# photo-trigger.net
KiCad netlist of a schematic drawn in EAGLE
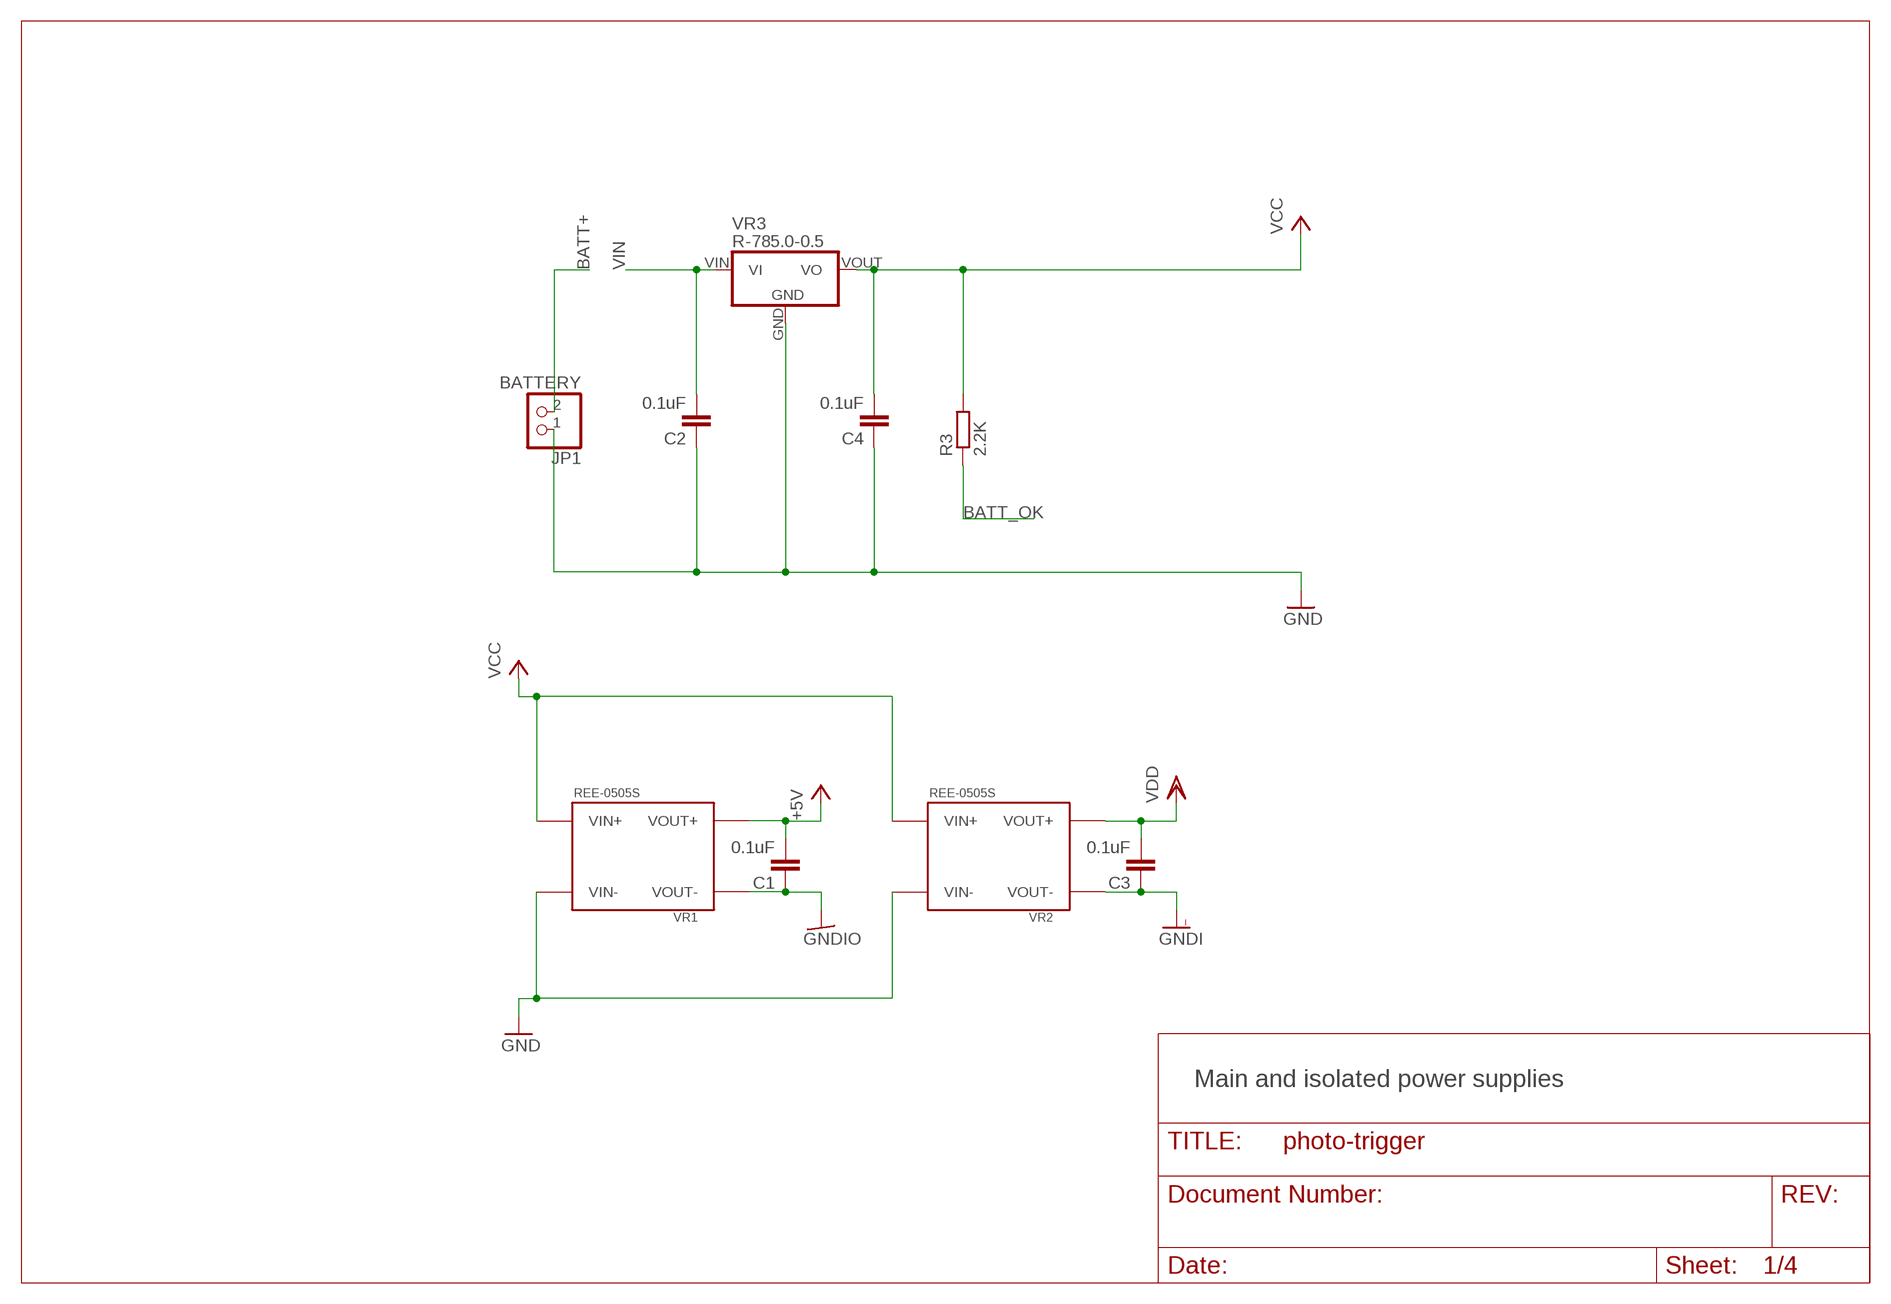
[diagram p0: schematic, sheet 1]
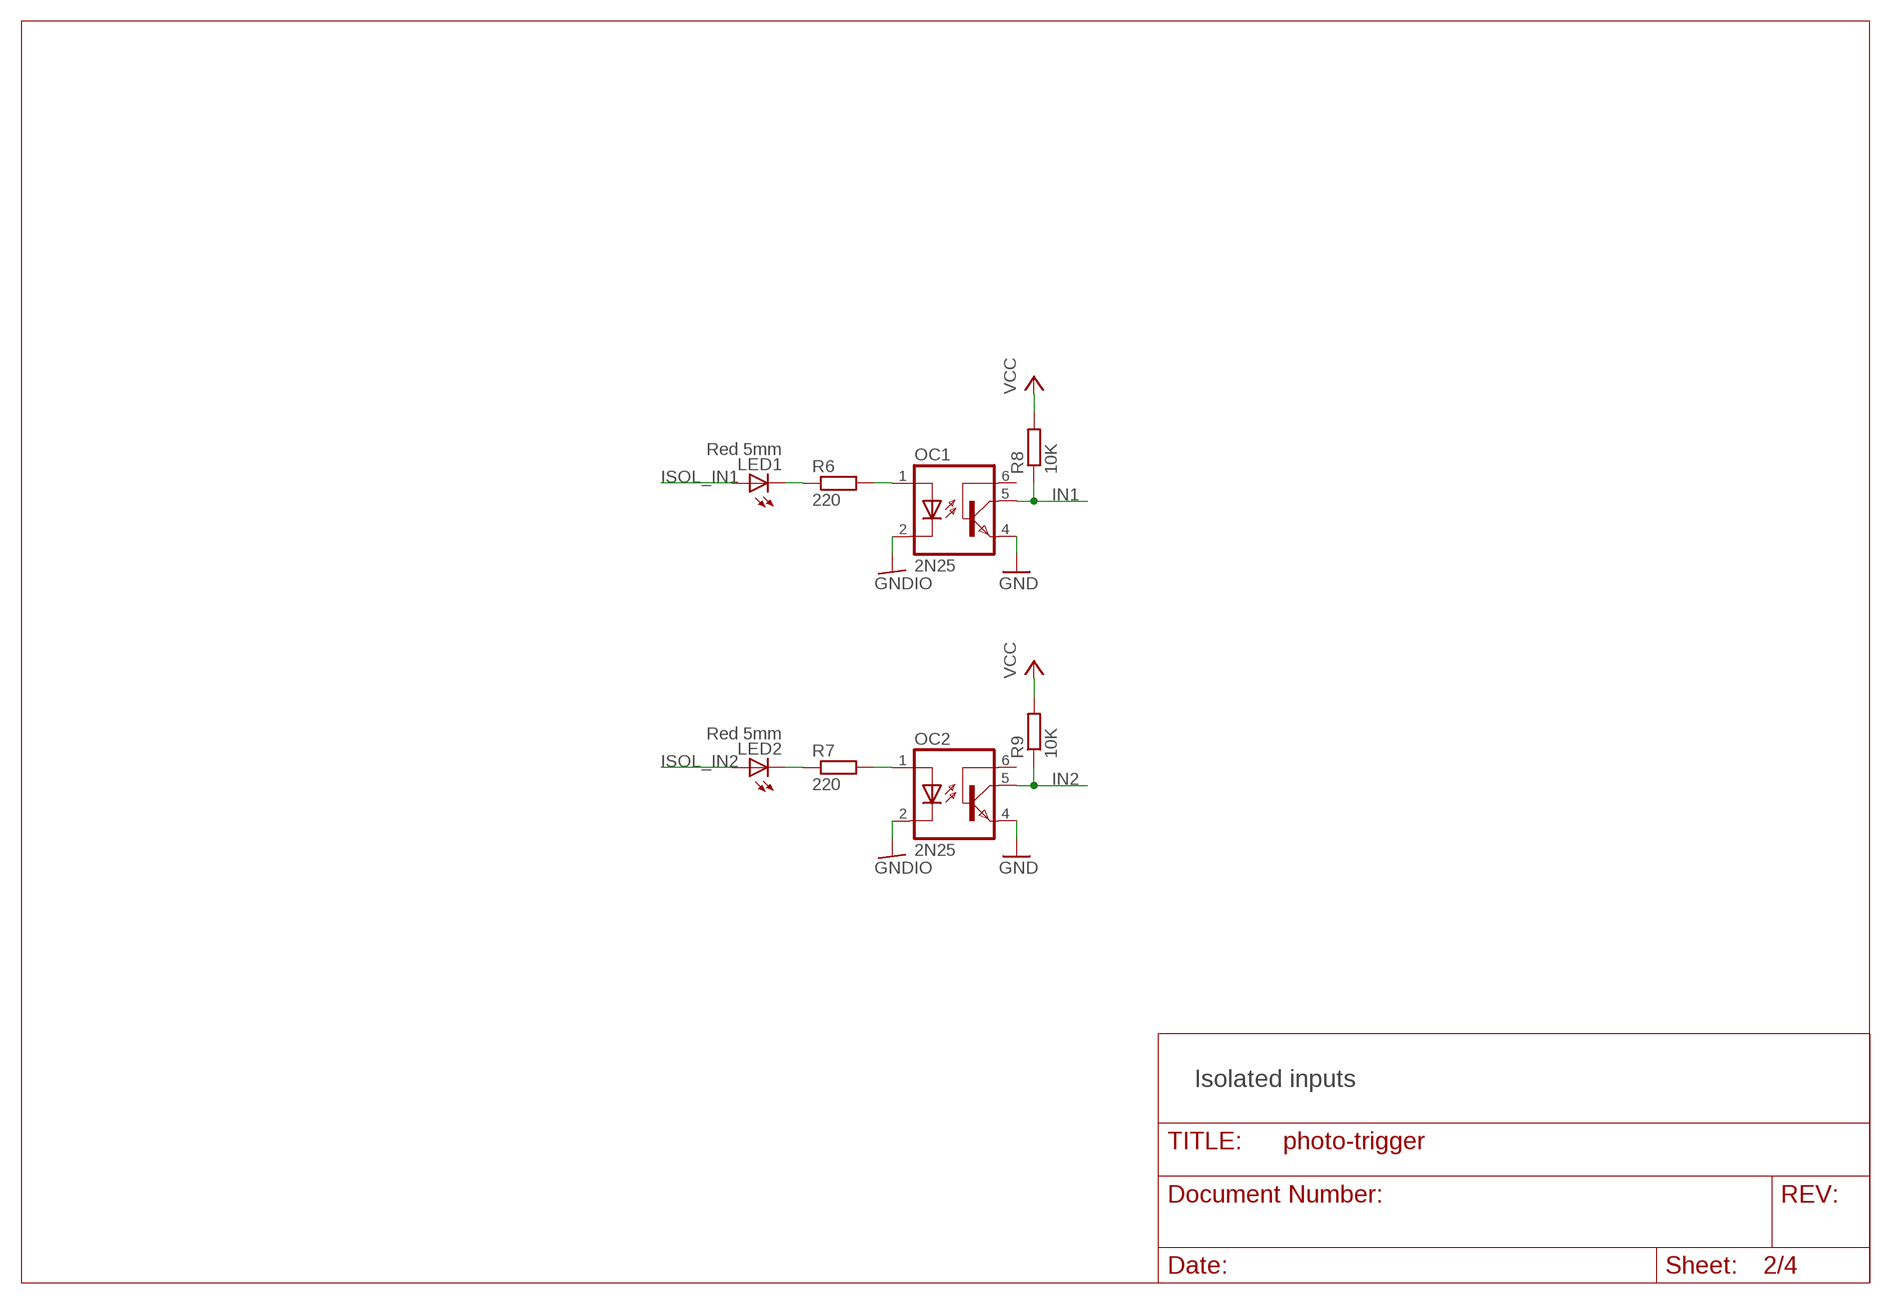
[diagram p1: schematic, sheet 2]
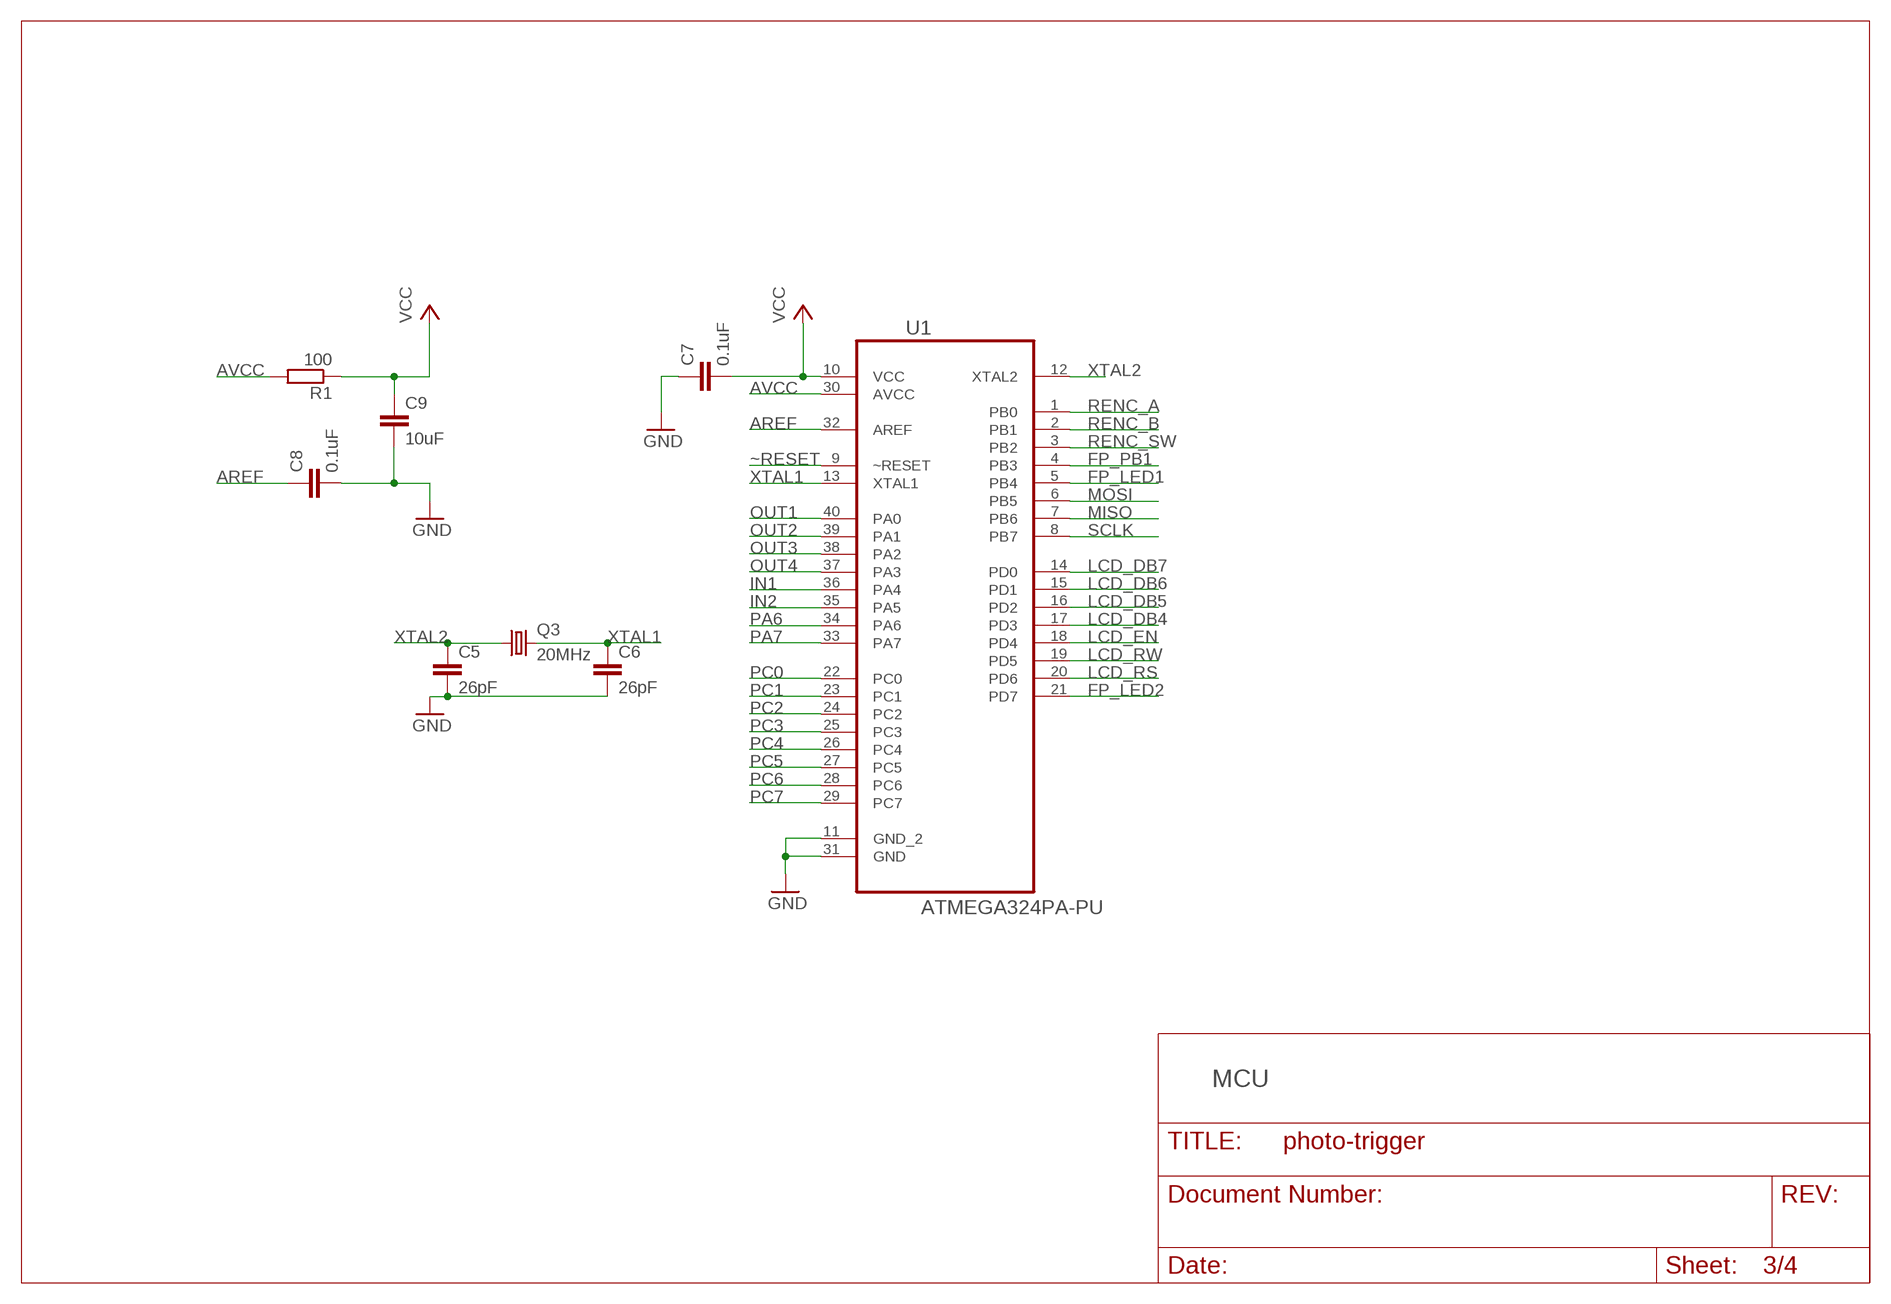
[diagram p2: schematic, sheet 3]
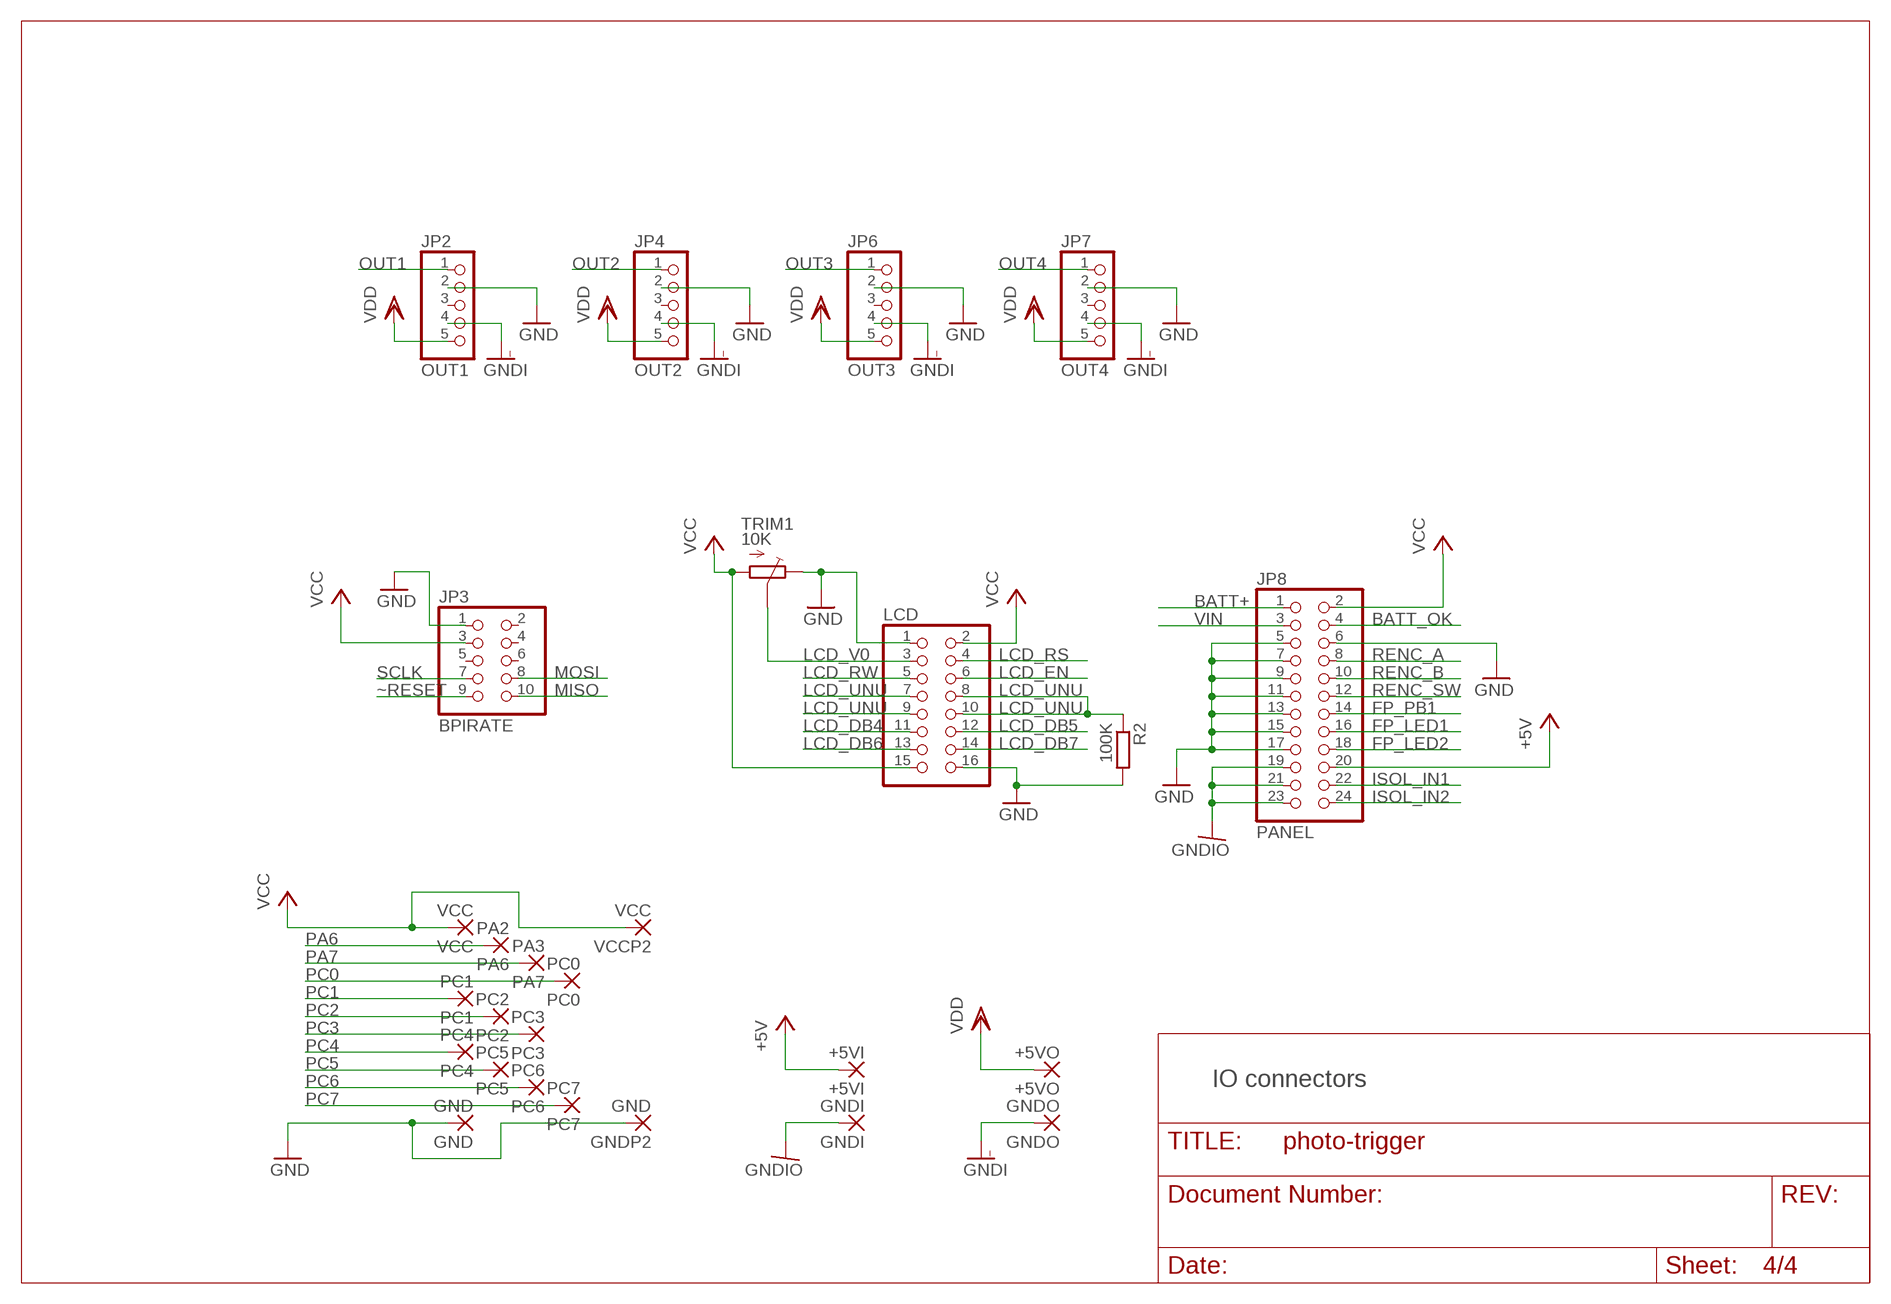
[diagram p3: schematic, sheet 4]

(export (version "E")
  (design (tool "Eeschema 10.0.6"))
  (components
    (comp (ref "C5")
      (value "26pF")
      (footprint "eagle-import:C025-025X050")
      (libsource (lib "eagle-import") (part "C-EU025-025X050"))
    )
    (comp (ref "C6")
      (value "26pF")
      (footprint "eagle-import:C025-025X050")
      (libsource (lib "eagle-import") (part "C-EU025-025X050"))
    )
    (comp (ref "C7")
      (value "0.1uF")
      (footprint "eagle-import:C050-035X075")
      (libsource (lib "eagle-import") (part "C-EU050-035X075"))
    )
    (comp (ref "C8")
      (value "0.1uF")
      (footprint "eagle-import:C050-035X075")
      (libsource (lib "eagle-import") (part "C-EU050-035X075"))
    )
    (comp (ref "C9")
      (value "10uF")
      (footprint "eagle-import:C050-035X075")
      (libsource (lib "eagle-import") (part "C-EU050-035X075"))
    )
    (comp (ref "Q3")
      (value "20MHz")
      (footprint "eagle-import:HC49_S")
      (libsource (lib "eagle-import") (part "CRYSTALHC49S"))
    )
    (comp (ref "R1")
      (value "100")
      (footprint "eagle-import:0207_10")
      (libsource (lib "eagle-import") (part "R-EU_0207/10"))
    )
    (comp (ref "U1")
      (value "ATMEGA324PA-PU")
      (footprint "eagle-import:DIP254P1524X482-40")
      (libsource (lib "eagle-import") (part "ATMEGA324PA-PU"))
    )
    (comp (ref "LED1")
      (value "Red 5mm")
      (footprint "eagle-import:LED5MM")
      (libsource (lib "eagle-import") (part "LED5MM"))
    )
    (comp (ref "LED2")
      (value "Red 5mm")
      (footprint "eagle-import:LED5MM")
      (libsource (lib "eagle-import") (part "LED5MM"))
    )
    (comp (ref "OC1")
      (value "2N25")
      (footprint "eagle-import:DIL-06")
      (libsource (lib "eagle-import") (part "2N25"))
    )
    (comp (ref "OC2")
      (value "2N25")
      (footprint "eagle-import:DIL-06")
      (libsource (lib "eagle-import") (part "2N25"))
    )
    (comp (ref "R6")
      (value "220")
      (footprint "eagle-import:0207_10")
      (libsource (lib "eagle-import") (part "resistor_R-EU_0207/10"))
    )
    (comp (ref "R7")
      (value "220")
      (footprint "eagle-import:0207_10")
      (libsource (lib "eagle-import") (part "resistor_R-EU_0207/10"))
    )
    (comp (ref "R8")
      (value "10K")
      (footprint "eagle-import:0207_10")
      (libsource (lib "eagle-import") (part "resistor_R-EU_0207/10"))
    )
    (comp (ref "R9")
      (value "10K")
      (footprint "eagle-import:0207_10")
      (libsource (lib "eagle-import") (part "resistor_R-EU_0207/10"))
    )
    (comp (ref "C1")
      (value "0.1uF")
      (footprint "eagle-import:C050-035X075")
      (libsource (lib "eagle-import") (part "C-EU050-035X075"))
    )
    (comp (ref "C2")
      (value "0.1uF")
      (footprint "eagle-import:C050-035X075")
      (libsource (lib "eagle-import") (part "C-EU050-035X075"))
    )
    (comp (ref "C3")
      (value "0.1uF")
      (footprint "eagle-import:C050-035X075")
      (libsource (lib "eagle-import") (part "C-EU050-035X075"))
    )
    (comp (ref "C4")
      (value "0.1uF")
      (footprint "eagle-import:C050-035X075")
      (libsource (lib "eagle-import") (part "C-EU050-035X075"))
    )
    (comp (ref "JP1")
      (value "BATTERY")
      (footprint "eagle-import:1X02")
      (libsource (lib "eagle-import") (part "PINHD-1X2"))
    )
    (comp (ref "R3")
      (value "2.2K")
      (footprint "eagle-import:0207_10")
      (libsource (lib "eagle-import") (part "R-EU_0207/10"))
    )
    (comp (ref "VR1")
      (value "REE-0505S")
      (footprint "eagle-import:RECOM-REE")
      (libsource (lib "eagle-import") (part "RECOM-REE-0505S"))
    )
    (comp (ref "VR2")
      (value "REE-0505S")
      (footprint "eagle-import:RECOM-REE")
      (libsource (lib "eagle-import") (part "RECOM-REE-0505S"))
    )
    (comp (ref "VR3")
      (value "R-785.0-0.5")
      (footprint "eagle-import:RECOM-R78")
      (libsource (lib "eagle-import") (part "RECOM-R-785.0-0.5"))
    )
    (comp (ref "+5VI")
      (value "+5VI")
      (footprint "eagle-import:1,6_0,9")
      (libsource (lib "eagle-import") (part "1,6/0,9"))
    )
    (comp (ref "+5VO")
      (value "+5VO")
      (footprint "eagle-import:1,6_0,9")
      (libsource (lib "eagle-import") (part "1,6/0,9"))
    )
    (comp (ref "GND")
      (value "GND")
      (footprint "eagle-import:1,6_0,9")
      (libsource (lib "eagle-import") (part "1,6/0,9"))
    )
    (comp (ref "GNDI")
      (value "GNDI")
      (footprint "eagle-import:1,6_0,9")
      (libsource (lib "eagle-import") (part "1,6/0,9"))
    )
    (comp (ref "GNDO")
      (value "GNDO")
      (footprint "eagle-import:1,6_0,9")
      (libsource (lib "eagle-import") (part "1,6/0,9"))
    )
    (comp (ref "GNDP2")
      (value "GND")
      (footprint "eagle-import:1,6_0,9")
      (libsource (lib "eagle-import") (part "1,6/0,9"))
    )
    (comp (ref "JP2")
      (value "OUT1")
      (footprint "eagle-import:1X05")
      (libsource (lib "eagle-import") (part "PINHD-1X5"))
    )
    (comp (ref "JP3")
      (value "BPIRATE")
      (footprint "eagle-import:2X05")
      (libsource (lib "eagle-import") (part "PINHD-2X5"))
    )
    (comp (ref "JP4")
      (value "OUT2")
      (footprint "eagle-import:1X05")
      (libsource (lib "eagle-import") (part "PINHD-1X5"))
    )
    (comp (ref "JP6")
      (value "OUT3")
      (footprint "eagle-import:1X05")
      (libsource (lib "eagle-import") (part "PINHD-1X5"))
    )
    (comp (ref "JP7")
      (value "OUT4")
      (footprint "eagle-import:1X05")
      (libsource (lib "eagle-import") (part "PINHD-1X5"))
    )
    (comp (ref "JP8")
      (value "PANEL")
      (footprint "eagle-import:2X12")
      (libsource (lib "eagle-import") (part "PINHD-2X12"))
    )
    (comp (ref "LCD")
      (value "PINHD-2X8")
      (footprint "eagle-import:2X08")
      (libsource (lib "eagle-import") (part "PINHD-2X8"))
    )
    (comp (ref "PA6")
      (value "PA2")
      (footprint "eagle-import:1,6_0,9")
      (libsource (lib "eagle-import") (part "1,6/0,9"))
    )
    (comp (ref "PA7")
      (value "PA3")
      (footprint "eagle-import:1,6_0,9")
      (libsource (lib "eagle-import") (part "1,6/0,9"))
    )
    (comp (ref "PC0")
      (value "PC0")
      (footprint "eagle-import:1,6_0,9")
      (libsource (lib "eagle-import") (part "1,6/0,9"))
    )
    (comp (ref "PC1")
      (value "PC1")
      (footprint "eagle-import:1,6_0,9")
      (libsource (lib "eagle-import") (part "1,6/0,9"))
    )
    (comp (ref "PC2")
      (value "PC2")
      (footprint "eagle-import:1,6_0,9")
      (libsource (lib "eagle-import") (part "1,6/0,9"))
    )
    (comp (ref "PC3")
      (value "PC3")
      (footprint "eagle-import:1,6_0,9")
      (libsource (lib "eagle-import") (part "1,6/0,9"))
    )
    (comp (ref "PC4")
      (value "PC4")
      (footprint "eagle-import:1,6_0,9")
      (libsource (lib "eagle-import") (part "1,6/0,9"))
    )
    (comp (ref "PC5")
      (value "PC5")
      (footprint "eagle-import:1,6_0,9")
      (libsource (lib "eagle-import") (part "1,6/0,9"))
    )
    (comp (ref "PC6")
      (value "PC6")
      (footprint "eagle-import:1,6_0,9")
      (libsource (lib "eagle-import") (part "1,6/0,9"))
    )
    (comp (ref "PC7")
      (value "PC7")
      (footprint "eagle-import:1,6_0,9")
      (libsource (lib "eagle-import") (part "1,6/0,9"))
    )
    (comp (ref "R2")
      (value "100K")
      (footprint "eagle-import:0207_10")
      (libsource (lib "eagle-import") (part "R-EU_0207/10"))
    )
    (comp (ref "TRIM1")
      (value "10K")
      (footprint "eagle-import:VISHAY-TRIM-63M-T607")
      (libsource (lib "eagle-import") (part "VISHAY-63M-T607"))
    )
    (comp (ref "VCC")
      (value "VCC")
      (footprint "eagle-import:1,6_0,9")
      (libsource (lib "eagle-import") (part "1,6/0,9"))
    )
    (comp (ref "VCCP2")
      (value "VCC")
      (footprint "eagle-import:1,6_0,9")
      (libsource (lib "eagle-import") (part "1,6/0,9"))
    )
  )
  (nets
    (net (code "1") (name "+5V") (class "Default")
      (node (ref "+5VI") (pin "1") (pinfunction "P_1") (pintype "passive"))
      (node (ref "C1") (pin "2") (pinfunction "2_2") (pintype "passive"))
      (node (ref "JP8") (pin "20") (pinfunction "20_20") (pintype "passive"))
      (node (ref "VR1") (pin "VOUT+") (pinfunction "VOUT+_VOUT+") (pintype "bidirectional"))
    )
    (net (code "2") (name "AREF") (class "Default")
      (node (ref "C8") (pin "1") (pinfunction "1_1") (pintype "passive"))
      (node (ref "U1") (pin "32") (pinfunction "AREF_32") (pintype "input"))
    )
    (net (code "3") (name "AVCC") (class "Default")
      (node (ref "R1") (pin "2") (pinfunction "2_2") (pintype "passive"))
      (node (ref "U1") (pin "30") (pinfunction "AVCC_30") (pintype "power_in"))
    )
    (net (code "4") (name "BATT+") (class "Default")
      (node (ref "JP1") (pin "2") (pinfunction "2_2") (pintype "passive"))
      (node (ref "JP8") (pin "1") (pinfunction "1_1") (pintype "passive"))
    )
    (net (code "5") (name "BATT_OK") (class "Default")
      (node (ref "JP8") (pin "4") (pinfunction "4_4") (pintype "passive"))
      (node (ref "R3") (pin "1") (pinfunction "1_1") (pintype "passive"))
    )
    (net (code "6") (name "FP_LED1") (class "Default")
      (node (ref "JP8") (pin "16") (pinfunction "16_16") (pintype "passive"))
      (node (ref "U1") (pin "5") (pinfunction "PB4_5") (pintype "bidirectional"))
    )
    (net (code "7") (name "FP_LED2") (class "Default")
      (node (ref "JP8") (pin "18") (pinfunction "18_18") (pintype "passive"))
      (node (ref "U1") (pin "21") (pinfunction "PD7_21") (pintype "bidirectional"))
    )
    (net (code "8") (name "FP_PB1") (class "Default")
      (node (ref "JP8") (pin "14") (pinfunction "14_14") (pintype "passive"))
      (node (ref "U1") (pin "4") (pinfunction "PB3_4") (pintype "bidirectional"))
    )
    (net (code "9") (name "GND") (class "Default")
      (node (ref "C2") (pin "1") (pinfunction "1_1") (pintype "passive"))
      (node (ref "C4") (pin "1") (pinfunction "1_1") (pintype "passive"))
      (node (ref "C5") (pin "2") (pinfunction "2_2") (pintype "passive"))
      (node (ref "C6") (pin "2") (pinfunction "2_2") (pintype "passive"))
      (node (ref "C7") (pin "1") (pinfunction "1_1") (pintype "passive"))
      (node (ref "C8") (pin "2") (pinfunction "2_2") (pintype "passive"))
      (node (ref "C9") (pin "2") (pinfunction "2_2") (pintype "passive"))
      (node (ref "GND") (pin "1") (pinfunction "P_1") (pintype "passive"))
      (node (ref "GNDP2") (pin "1") (pinfunction "P_1") (pintype "passive"))
      (node (ref "JP1") (pin "1") (pinfunction "1_1") (pintype "passive"))
      (node (ref "JP2") (pin "2") (pinfunction "2_2") (pintype "passive"))
      (node (ref "JP3") (pin "1") (pinfunction "1_1") (pintype "passive"))
      (node (ref "JP4") (pin "2") (pinfunction "2_2") (pintype "passive"))
      (node (ref "JP6") (pin "2") (pinfunction "2_2") (pintype "passive"))
      (node (ref "JP7") (pin "2") (pinfunction "2_2") (pintype "passive"))
      (node (ref "JP8") (pin "11") (pinfunction "11_11") (pintype "passive"))
      (node (ref "JP8") (pin "13") (pinfunction "13_13") (pintype "passive"))
      (node (ref "JP8") (pin "15") (pinfunction "15_15") (pintype "passive"))
      (node (ref "JP8") (pin "17") (pinfunction "17_17") (pintype "passive"))
      (node (ref "JP8") (pin "5") (pinfunction "5_5") (pintype "passive"))
      (node (ref "JP8") (pin "6") (pinfunction "6_6") (pintype "passive"))
      (node (ref "JP8") (pin "7") (pinfunction "7_7") (pintype "passive"))
      (node (ref "JP8") (pin "9") (pinfunction "9_9") (pintype "passive"))
      (node (ref "LCD") (pin "1") (pinfunction "1_1") (pintype "passive"))
      (node (ref "LCD") (pin "16") (pinfunction "16_16") (pintype "passive"))
      (node (ref "OC1") (pin "4") (pinfunction "EMI_4") (pintype "passive"))
      (node (ref "OC2") (pin "4") (pinfunction "EMI_4") (pintype "passive"))
      (node (ref "R2") (pin "2") (pinfunction "2_2") (pintype "passive"))
      (node (ref "TRIM1") (pin "P$3") (pinfunction "E_P$3") (pintype "passive"))
      (node (ref "U1") (pin "11") (pinfunction "GND_2_11") (pintype "passive"))
      (node (ref "U1") (pin "31") (pinfunction "GND_31") (pintype "passive"))
      (node (ref "VR1") (pin "VIN-") (pinfunction "VIN-_VIN-") (pintype "bidirectional"))
      (node (ref "VR2") (pin "VIN-") (pinfunction "VIN-_VIN-") (pintype "bidirectional"))
      (node (ref "VR3") (pin "GND") (pinfunction "GND_GND") (pintype "passive"))
    )
    (net (code "10") (name "GNDI") (class "Default")
      (node (ref "C3") (pin "1") (pinfunction "1_1") (pintype "passive"))
      (node (ref "GNDO") (pin "1") (pinfunction "P_1") (pintype "passive"))
      (node (ref "JP2") (pin "4") (pinfunction "4_4") (pintype "passive"))
      (node (ref "JP4") (pin "4") (pinfunction "4_4") (pintype "passive"))
      (node (ref "JP6") (pin "4") (pinfunction "4_4") (pintype "passive"))
      (node (ref "JP7") (pin "4") (pinfunction "4_4") (pintype "passive"))
      (node (ref "VR2") (pin "VOUT-") (pinfunction "VOUT-_VOUT-") (pintype "bidirectional"))
    )
    (net (code "11") (name "GNDIO") (class "Default")
      (node (ref "C1") (pin "1") (pinfunction "1_1") (pintype "passive"))
      (node (ref "GNDI") (pin "1") (pinfunction "P_1") (pintype "passive"))
      (node (ref "JP8") (pin "19") (pinfunction "19_19") (pintype "passive"))
      (node (ref "JP8") (pin "21") (pinfunction "21_21") (pintype "passive"))
      (node (ref "JP8") (pin "23") (pinfunction "23_23") (pintype "passive"))
      (node (ref "OC1") (pin "2") (pinfunction "C_2") (pintype "passive"))
      (node (ref "OC2") (pin "2") (pinfunction "C_2") (pintype "passive"))
      (node (ref "VR1") (pin "VOUT-") (pinfunction "VOUT-_VOUT-") (pintype "bidirectional"))
    )
    (net (code "12") (name "IN1") (class "Default")
      (node (ref "OC1") (pin "5") (pinfunction "COL_5") (pintype "passive"))
      (node (ref "R8") (pin "1") (pinfunction "1_1") (pintype "passive"))
      (node (ref "U1") (pin "36") (pinfunction "PA4_36") (pintype "bidirectional"))
    )
    (net (code "13") (name "IN2") (class "Default")
      (node (ref "OC2") (pin "5") (pinfunction "COL_5") (pintype "passive"))
      (node (ref "R9") (pin "1") (pinfunction "1_1") (pintype "passive"))
      (node (ref "U1") (pin "35") (pinfunction "PA5_35") (pintype "bidirectional"))
    )
    (net (code "14") (name "ISOL_IN1") (class "Default")
      (node (ref "JP8") (pin "22") (pinfunction "22_22") (pintype "passive"))
      (node (ref "LED1") (pin "A") (pinfunction "A_A") (pintype "passive"))
    )
    (net (code "15") (name "ISOL_IN2") (class "Default")
      (node (ref "JP8") (pin "24") (pinfunction "24_24") (pintype "passive"))
      (node (ref "LED2") (pin "A") (pinfunction "A_A") (pintype "passive"))
    )
    (net (code "16") (name "LCD_DB4") (class "Default")
      (node (ref "LCD") (pin "11") (pinfunction "11_11") (pintype "passive"))
      (node (ref "U1") (pin "17") (pinfunction "PD3_17") (pintype "bidirectional"))
    )
    (net (code "17") (name "LCD_DB5") (class "Default")
      (node (ref "LCD") (pin "12") (pinfunction "12_12") (pintype "passive"))
      (node (ref "U1") (pin "16") (pinfunction "PD2_16") (pintype "bidirectional"))
    )
    (net (code "18") (name "LCD_DB6") (class "Default")
      (node (ref "LCD") (pin "13") (pinfunction "13_13") (pintype "passive"))
      (node (ref "U1") (pin "15") (pinfunction "PD1_15") (pintype "bidirectional"))
    )
    (net (code "19") (name "LCD_DB7") (class "Default")
      (node (ref "LCD") (pin "14") (pinfunction "14_14") (pintype "passive"))
      (node (ref "U1") (pin "14") (pinfunction "PD0_14") (pintype "bidirectional"))
    )
    (net (code "20") (name "LCD_EN") (class "Default")
      (node (ref "LCD") (pin "6") (pinfunction "6_6") (pintype "passive"))
      (node (ref "U1") (pin "18") (pinfunction "PD4_18") (pintype "bidirectional"))
    )
    (net (code "21") (name "LCD_RS") (class "Default")
      (node (ref "LCD") (pin "4") (pinfunction "4_4") (pintype "passive"))
      (node (ref "U1") (pin "20") (pinfunction "PD6_20") (pintype "bidirectional"))
    )
    (net (code "22") (name "LCD_RW") (class "Default")
      (node (ref "LCD") (pin "5") (pinfunction "5_5") (pintype "passive"))
      (node (ref "U1") (pin "19") (pinfunction "PD5_19") (pintype "bidirectional"))
    )
    (net (code "23") (name "LCD_UNU") (class "Default")
      (node (ref "LCD") (pin "10") (pinfunction "10_10") (pintype "passive"))
      (node (ref "LCD") (pin "7") (pinfunction "7_7") (pintype "passive"))
      (node (ref "LCD") (pin "8") (pinfunction "8_8") (pintype "passive"))
      (node (ref "LCD") (pin "9") (pinfunction "9_9") (pintype "passive"))
      (node (ref "R2") (pin "1") (pinfunction "1_1") (pintype "passive"))
    )
    (net (code "24") (name "LCD_V0") (class "Default")
      (node (ref "LCD") (pin "3") (pinfunction "3_3") (pintype "passive"))
      (node (ref "TRIM1") (pin "P$2") (pinfunction "S_P$2") (pintype "passive"))
    )
    (net (code "25") (name "MISO") (class "Default")
      (node (ref "JP3") (pin "10") (pinfunction "10_10") (pintype "passive"))
      (node (ref "U1") (pin "7") (pinfunction "PB6_7") (pintype "bidirectional"))
    )
    (net (code "26") (name "MOSI") (class "Default")
      (node (ref "JP3") (pin "8") (pinfunction "8_8") (pintype "passive"))
      (node (ref "U1") (pin "6") (pinfunction "PB5_6") (pintype "bidirectional"))
    )
    (net (code "27") (name "Net-(LED1-C)") (class "Default")
      (node (ref "LED1") (pin "K") (pinfunction "C_K") (pintype "passive"))
      (node (ref "R6") (pin "1") (pinfunction "1_1") (pintype "passive"))
    )
    (net (code "28") (name "Net-(LED2-C)") (class "Default")
      (node (ref "LED2") (pin "K") (pinfunction "C_K") (pintype "passive"))
      (node (ref "R7") (pin "1") (pinfunction "1_1") (pintype "passive"))
    )
    (net (code "29") (name "Net-(OC1-A)") (class "Default")
      (node (ref "OC1") (pin "1") (pinfunction "A_1") (pintype "passive"))
      (node (ref "R6") (pin "2") (pinfunction "2_2") (pintype "passive"))
    )
    (net (code "30") (name "Net-(OC2-A)") (class "Default")
      (node (ref "OC2") (pin "1") (pinfunction "A_1") (pintype "passive"))
      (node (ref "R7") (pin "2") (pinfunction "2_2") (pintype "passive"))
    )
    (net (code "31") (name "OUT1") (class "Default")
      (node (ref "JP2") (pin "1") (pinfunction "1_1") (pintype "passive"))
      (node (ref "U1") (pin "40") (pinfunction "PA0_40") (pintype "bidirectional"))
    )
    (net (code "32") (name "OUT2") (class "Default")
      (node (ref "JP4") (pin "1") (pinfunction "1_1") (pintype "passive"))
      (node (ref "U1") (pin "39") (pinfunction "PA1_39") (pintype "bidirectional"))
    )
    (net (code "33") (name "OUT3") (class "Default")
      (node (ref "JP6") (pin "1") (pinfunction "1_1") (pintype "passive"))
      (node (ref "U1") (pin "38") (pinfunction "PA2_38") (pintype "bidirectional"))
    )
    (net (code "34") (name "OUT4") (class "Default")
      (node (ref "JP7") (pin "1") (pinfunction "1_1") (pintype "passive"))
      (node (ref "U1") (pin "37") (pinfunction "PA3_37") (pintype "bidirectional"))
    )
    (net (code "35") (name "PA6") (class "Default")
      (node (ref "PA6") (pin "1") (pinfunction "P_1") (pintype "passive"))
      (node (ref "U1") (pin "34") (pinfunction "PA6_34") (pintype "bidirectional"))
    )
    (net (code "36") (name "PA7") (class "Default")
      (node (ref "PA7") (pin "1") (pinfunction "P_1") (pintype "passive"))
      (node (ref "U1") (pin "33") (pinfunction "PA7_33") (pintype "bidirectional"))
    )
    (net (code "37") (name "PC0") (class "Default")
      (node (ref "PC0") (pin "1") (pinfunction "P_1") (pintype "passive"))
      (node (ref "U1") (pin "22") (pinfunction "PC0_22") (pintype "bidirectional"))
    )
    (net (code "38") (name "PC1") (class "Default")
      (node (ref "PC1") (pin "1") (pinfunction "P_1") (pintype "passive"))
      (node (ref "U1") (pin "23") (pinfunction "PC1_23") (pintype "bidirectional"))
    )
    (net (code "39") (name "PC2") (class "Default")
      (node (ref "PC2") (pin "1") (pinfunction "P_1") (pintype "passive"))
      (node (ref "U1") (pin "24") (pinfunction "PC2_24") (pintype "bidirectional"))
    )
    (net (code "40") (name "PC3") (class "Default")
      (node (ref "PC3") (pin "1") (pinfunction "P_1") (pintype "passive"))
      (node (ref "U1") (pin "25") (pinfunction "PC3_25") (pintype "bidirectional"))
    )
    (net (code "41") (name "PC4") (class "Default")
      (node (ref "PC4") (pin "1") (pinfunction "P_1") (pintype "passive"))
      (node (ref "U1") (pin "26") (pinfunction "PC4_26") (pintype "bidirectional"))
    )
    (net (code "42") (name "PC5") (class "Default")
      (node (ref "PC5") (pin "1") (pinfunction "P_1") (pintype "passive"))
      (node (ref "U1") (pin "27") (pinfunction "PC5_27") (pintype "bidirectional"))
    )
    (net (code "43") (name "PC6") (class "Default")
      (node (ref "PC6") (pin "1") (pinfunction "P_1") (pintype "passive"))
      (node (ref "U1") (pin "28") (pinfunction "PC6_28") (pintype "bidirectional"))
    )
    (net (code "44") (name "PC7") (class "Default")
      (node (ref "PC7") (pin "1") (pinfunction "P_1") (pintype "passive"))
      (node (ref "U1") (pin "29") (pinfunction "PC7_29") (pintype "bidirectional"))
    )
    (net (code "45") (name "RENC_A") (class "Default")
      (node (ref "JP8") (pin "8") (pinfunction "8_8") (pintype "passive"))
      (node (ref "U1") (pin "1") (pinfunction "PB0_1") (pintype "bidirectional"))
    )
    (net (code "46") (name "RENC_B") (class "Default")
      (node (ref "JP8") (pin "10") (pinfunction "10_10") (pintype "passive"))
      (node (ref "U1") (pin "2") (pinfunction "PB1_2") (pintype "bidirectional"))
    )
    (net (code "47") (name "RENC_SW") (class "Default")
      (node (ref "JP8") (pin "12") (pinfunction "12_12") (pintype "passive"))
      (node (ref "U1") (pin "3") (pinfunction "PB2_3") (pintype "bidirectional"))
    )
    (net (code "48") (name "SCLK") (class "Default")
      (node (ref "JP3") (pin "7") (pinfunction "7_7") (pintype "passive"))
      (node (ref "U1") (pin "8") (pinfunction "PB7_8") (pintype "bidirectional"))
    )
    (net (code "49") (name "VCC") (class "Default")
      (node (ref "C4") (pin "2") (pinfunction "2_2") (pintype "passive"))
      (node (ref "C7") (pin "2") (pinfunction "2_2") (pintype "passive"))
      (node (ref "C9") (pin "1") (pinfunction "1_1") (pintype "passive"))
      (node (ref "JP3") (pin "3") (pinfunction "3_3") (pintype "passive"))
      (node (ref "JP8") (pin "2") (pinfunction "2_2") (pintype "passive"))
      (node (ref "LCD") (pin "15") (pinfunction "15_15") (pintype "passive"))
      (node (ref "LCD") (pin "2") (pinfunction "2_2") (pintype "passive"))
      (node (ref "R1") (pin "1") (pinfunction "1_1") (pintype "passive"))
      (node (ref "R3") (pin "2") (pinfunction "2_2") (pintype "passive"))
      (node (ref "R8") (pin "2") (pinfunction "2_2") (pintype "passive"))
      (node (ref "R9") (pin "2") (pinfunction "2_2") (pintype "passive"))
      (node (ref "TRIM1") (pin "P$1") (pinfunction "A_P$1") (pintype "passive"))
      (node (ref "U1") (pin "10") (pinfunction "VCC_10") (pintype "power_in"))
      (node (ref "VCC") (pin "1") (pinfunction "P_1") (pintype "passive"))
      (node (ref "VCCP2") (pin "1") (pinfunction "P_1") (pintype "passive"))
      (node (ref "VR1") (pin "VIN+") (pinfunction "VIN+_VIN+") (pintype "bidirectional"))
      (node (ref "VR2") (pin "VIN+") (pinfunction "VIN+_VIN+") (pintype "bidirectional"))
      (node (ref "VR3") (pin "VOUT") (pinfunction "VO_VOUT") (pintype "passive"))
    )
    (net (code "50") (name "VDD") (class "Default")
      (node (ref "+5VO") (pin "1") (pinfunction "P_1") (pintype "passive"))
      (node (ref "C3") (pin "2") (pinfunction "2_2") (pintype "passive"))
      (node (ref "JP2") (pin "5") (pinfunction "5_5") (pintype "passive"))
      (node (ref "JP4") (pin "5") (pinfunction "5_5") (pintype "passive"))
      (node (ref "JP6") (pin "5") (pinfunction "5_5") (pintype "passive"))
      (node (ref "JP7") (pin "5") (pinfunction "5_5") (pintype "passive"))
      (node (ref "VR2") (pin "VOUT+") (pinfunction "VOUT+_VOUT+") (pintype "bidirectional"))
    )
    (net (code "51") (name "VIN") (class "Default")
      (node (ref "C2") (pin "2") (pinfunction "2_2") (pintype "passive"))
      (node (ref "JP8") (pin "3") (pinfunction "3_3") (pintype "passive"))
      (node (ref "VR3") (pin "VIN") (pinfunction "VI_VIN") (pintype "input"))
    )
    (net (code "52") (name "XTAL1") (class "Default")
      (node (ref "C6") (pin "1") (pinfunction "1_1") (pintype "passive"))
      (node (ref "Q3") (pin "2") (pinfunction "2_2") (pintype "passive"))
      (node (ref "U1") (pin "13") (pinfunction "XTAL1_13") (pintype "input"))
    )
    (net (code "53") (name "XTAL2") (class "Default")
      (node (ref "C5") (pin "1") (pinfunction "1_1") (pintype "passive"))
      (node (ref "Q3") (pin "1") (pinfunction "1_1") (pintype "passive"))
      (node (ref "U1") (pin "12") (pinfunction "XTAL2_12") (pintype "output"))
    )
    (net (code "54") (name "unconnected-(JP2-Pad3)") (class "Default")
      (node (ref "JP2") (pin "3") (pinfunction "3_3") (pintype "passive"))
    )
    (net (code "55") (name "unconnected-(JP3-Pad2)") (class "Default")
      (node (ref "JP3") (pin "2") (pinfunction "2_2") (pintype "passive"))
    )
    (net (code "56") (name "unconnected-(JP3-Pad4)") (class "Default")
      (node (ref "JP3") (pin "4") (pinfunction "4_4") (pintype "passive"))
    )
    (net (code "57") (name "unconnected-(JP3-Pad5)") (class "Default")
      (node (ref "JP3") (pin "5") (pinfunction "5_5") (pintype "passive"))
    )
    (net (code "58") (name "unconnected-(JP3-Pad6)") (class "Default")
      (node (ref "JP3") (pin "6") (pinfunction "6_6") (pintype "passive"))
    )
    (net (code "59") (name "unconnected-(JP4-Pad3)") (class "Default")
      (node (ref "JP4") (pin "3") (pinfunction "3_3") (pintype "passive"))
    )
    (net (code "60") (name "unconnected-(JP6-Pad3)") (class "Default")
      (node (ref "JP6") (pin "3") (pinfunction "3_3") (pintype "passive"))
    )
    (net (code "61") (name "unconnected-(JP7-Pad3)") (class "Default")
      (node (ref "JP7") (pin "3") (pinfunction "3_3") (pintype "passive"))
    )
    (net (code "62") (name "unconnected-(OC1-BAS-Pad6)") (class "Default")
      (node (ref "OC1") (pin "6") (pinfunction "BAS_6") (pintype "passive"))
    )
    (net (code "63") (name "unconnected-(OC2-BAS-Pad6)") (class "Default")
      (node (ref "OC2") (pin "6") (pinfunction "BAS_6") (pintype "passive"))
    )
    (net (code "64") (name "~{RESET}") (class "Default")
      (node (ref "JP3") (pin "9") (pinfunction "9_9") (pintype "passive"))
      (node (ref "U1") (pin "9") (pinfunction "~{RESET}_9") (pintype "input"))
    )
  )
)
